# lo-synth.net
KiCad netlist of a schematic drawn in Altium Designer
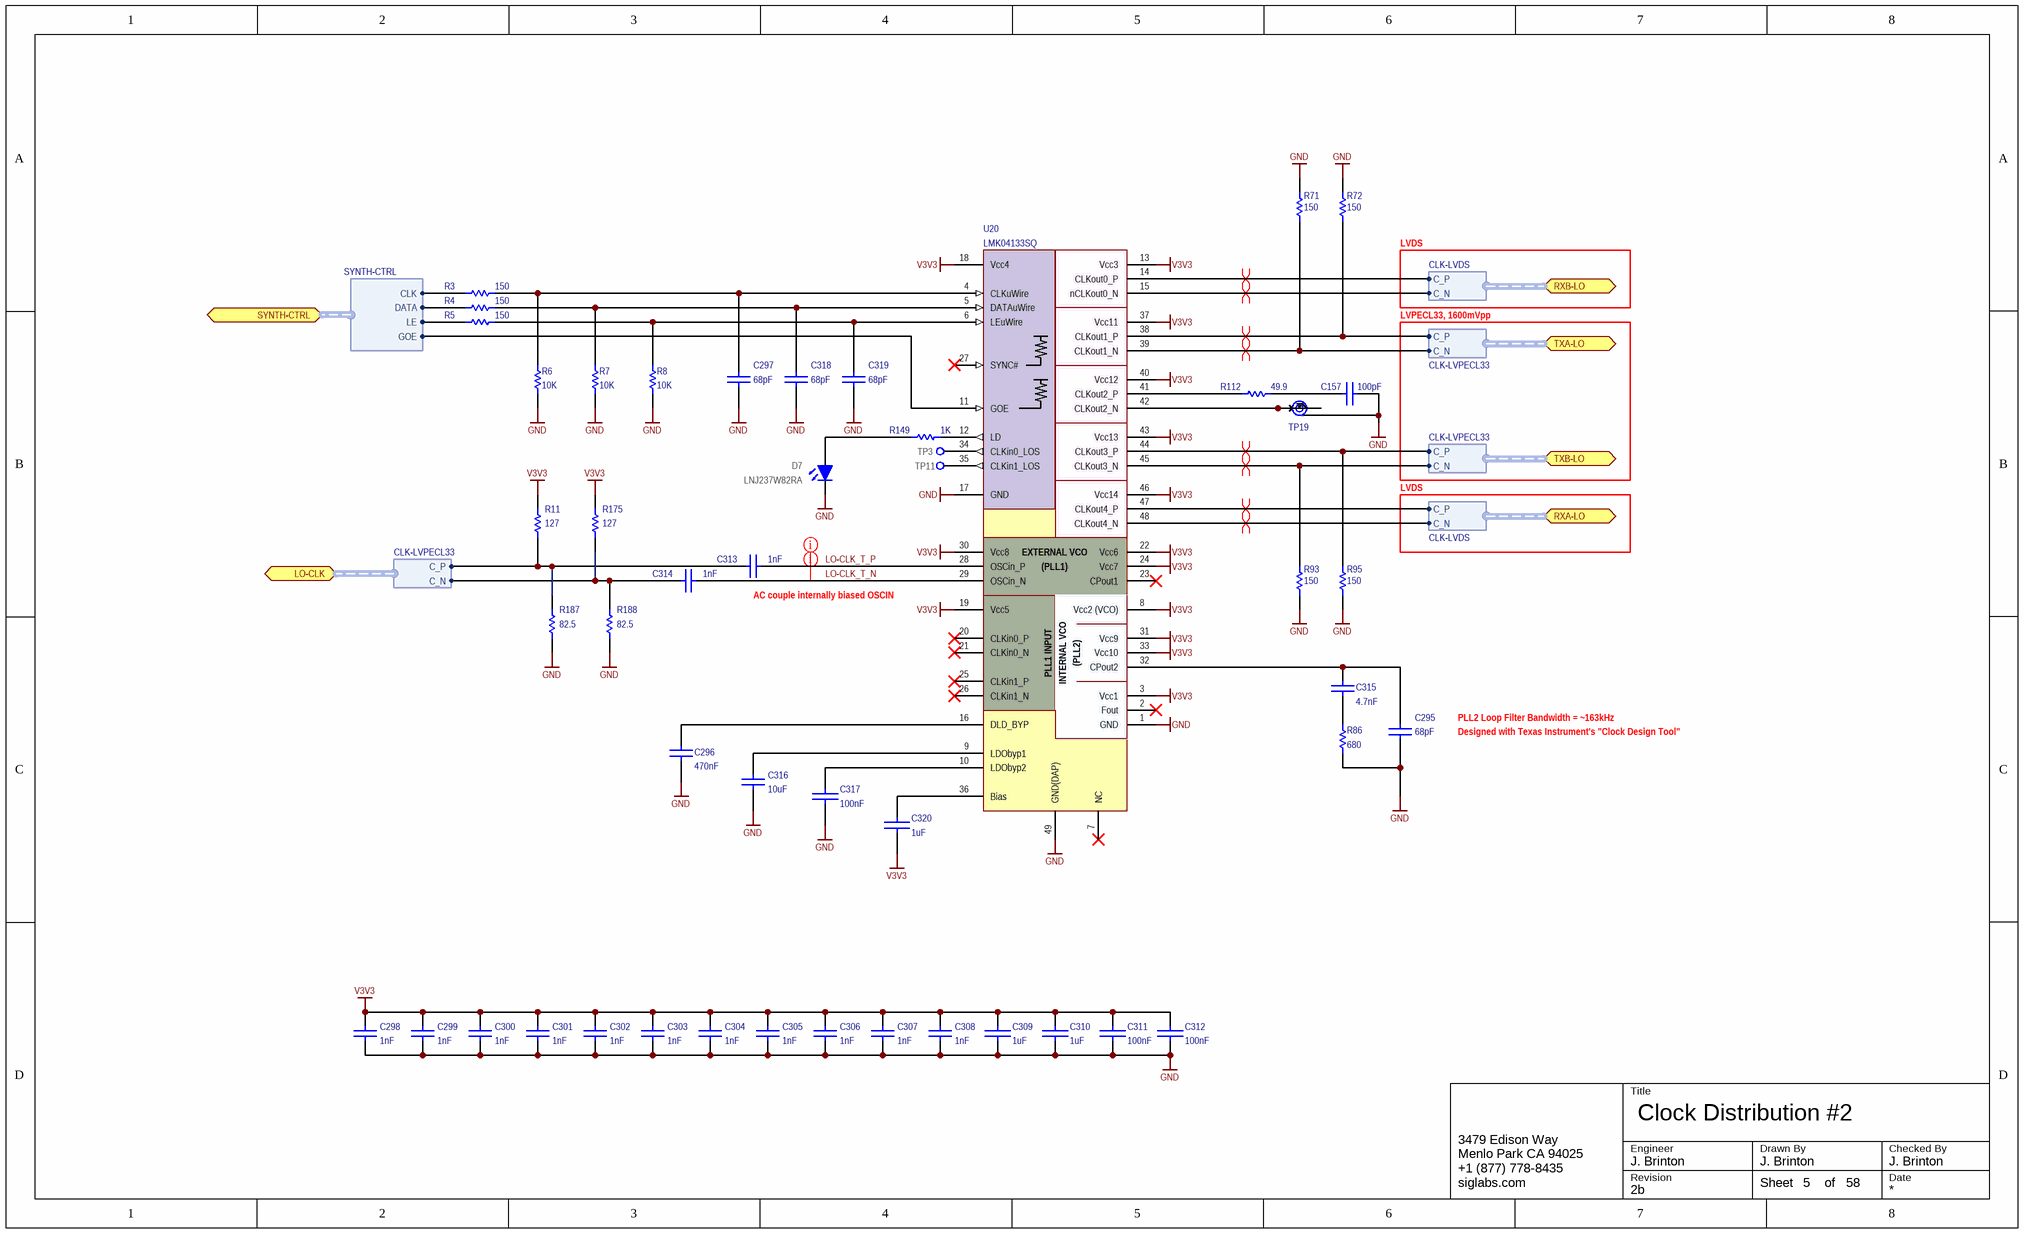
[diagram p0: lo-synth.SchDoc]

(export (version "E")
  (design (tool "Eeschema 10.0.6"))
  (components
    (comp (ref "C157")
      (value "100pF")
      (footprint "0402")
      (description "Ceramic Capacitor 100pF ±1% 25V NP0 0402")
      (fields (field (name "VOLTAGE") "25V") (field (name "MANUFACTURER") "Kemet"))
      (libsource (lib "generic") (part "CAP 0603"))
    )
    (comp (ref "C295")
      (value "68pF")
      (footprint "generic:0402")
      (description "Ceramic Capacitor 68pF ±2% 50V NP0 0402")
      (fields (field (name "VOLTAGE") "50V") (field (name "MANUFACTURER") "Murata"))
      (libsource (lib "Graviton") (part "CAP 0402"))
    )
    (comp (ref "C296")
      (value "470nF")
      (footprint "generic:0805")
      (description "Ceramic Capacitor 470nF ±10% 50V X7R 0805")
      (fields (field (name "VOLTAGE") "50V") (field (name "MANUFACTURER") "Kemet"))
      (libsource (lib "Graviton") (part "CAP 0402"))
    )
    (comp (ref "C297")
      (value "68pF")
      (footprint "generic:0402")
      (description "Ceramic Capacitor 68pF ±2% 50V NP0 0402")
      (fields (field (name "VOLTAGE") "50V") (field (name "MANUFACTURER") "Murata"))
      (libsource (lib "Graviton") (part "CAP 0402"))
    )
    (comp (ref "C298")
      (value "1nF")
      (footprint "generic:0402")
      (description "Ceramic Capacitor 1nF ±5% 50V NP0 0402")
      (fields (field (name "VOLTAGE") "50V") (field (name "MANUFACTURER") "Murata"))
      (libsource (lib "Graviton") (part "CAP 0402"))
    )
    (comp (ref "C299")
      (value "1nF")
      (footprint "generic:0402")
      (description "Ceramic Capacitor 1nF ±5% 50V NP0 0402")
      (fields (field (name "VOLTAGE") "50V") (field (name "MANUFACTURER") "Murata"))
      (libsource (lib "Graviton") (part "CAP 0402"))
    )
    (comp (ref "C300")
      (value "1nF")
      (footprint "generic:0402")
      (description "Ceramic Capacitor 1nF ±5% 50V NP0 0402")
      (fields (field (name "VOLTAGE") "50V") (field (name "MANUFACTURER") "Murata"))
      (libsource (lib "Graviton") (part "CAP 0402"))
    )
    (comp (ref "C301")
      (value "1nF")
      (footprint "generic:0402")
      (description "Ceramic Capacitor 1nF ±5% 50V NP0 0402")
      (fields (field (name "VOLTAGE") "50V") (field (name "MANUFACTURER") "Murata"))
      (libsource (lib "Graviton") (part "CAP 0402"))
    )
    (comp (ref "C302")
      (value "1nF")
      (footprint "generic:0402")
      (description "Ceramic Capacitor 1nF ±5% 50V NP0 0402")
      (fields (field (name "VOLTAGE") "50V") (field (name "MANUFACTURER") "Murata"))
      (libsource (lib "Graviton") (part "CAP 0402"))
    )
    (comp (ref "C303")
      (value "1nF")
      (footprint "generic:0402")
      (description "Ceramic Capacitor 1nF ±5% 50V NP0 0402")
      (fields (field (name "VOLTAGE") "50V") (field (name "MANUFACTURER") "Murata"))
      (libsource (lib "Graviton") (part "CAP 0402"))
    )
    (comp (ref "C304")
      (value "1nF")
      (footprint "generic:0402")
      (description "Ceramic Capacitor 1nF ±5% 50V NP0 0402")
      (fields (field (name "VOLTAGE") "50V") (field (name "MANUFACTURER") "Murata"))
      (libsource (lib "Graviton") (part "CAP 0402"))
    )
    (comp (ref "C305")
      (value "1nF")
      (footprint "generic:0402")
      (description "Ceramic Capacitor 1nF ±5% 50V NP0 0402")
      (fields (field (name "VOLTAGE") "50V") (field (name "MANUFACTURER") "Murata"))
      (libsource (lib "Graviton") (part "CAP 0402"))
    )
    (comp (ref "C306")
      (value "1nF")
      (footprint "generic:0402")
      (description "Ceramic Capacitor 1nF ±5% 50V NP0 0402")
      (fields (field (name "VOLTAGE") "50V") (field (name "MANUFACTURER") "Murata"))
      (libsource (lib "Graviton") (part "CAP 0402"))
    )
    (comp (ref "C307")
      (value "1nF")
      (footprint "generic:0402")
      (description "Ceramic Capacitor 1nF ±5% 50V NP0 0402")
      (fields (field (name "VOLTAGE") "50V") (field (name "MANUFACTURER") "Murata"))
      (libsource (lib "Graviton") (part "CAP 0402"))
    )
    (comp (ref "C308")
      (value "1nF")
      (footprint "generic:0402")
      (description "Ceramic Capacitor 1nF ±5% 50V NP0 0402")
      (fields (field (name "VOLTAGE") "50V") (field (name "MANUFACTURER") "Murata"))
      (libsource (lib "Graviton") (part "CAP 0402"))
    )
    (comp (ref "C309")
      (value "1uF")
      (footprint "generic:0402")
      (description "Ceramic Capacitor 1uF ±10% 10V X5R 0402")
      (fields (field (name "MANUFACTURER") "Murata") (field (name "TOLERANCE") "±10%"))
      (libsource (lib "*") (part "CAP"))
    )
    (comp (ref "C310")
      (value "1uF")
      (footprint "generic:0402")
      (description "Ceramic Capacitor 1uF ±10% 10V X5R 0402")
      (fields (field (name "MANUFACTURER") "Murata") (field (name "TOLERANCE") "±10%"))
      (libsource (lib "*") (part "CAP"))
    )
    (comp (ref "C311")
      (value "100nF")
      (footprint "generic:0402")
      (description "Ceramic Capacitor 100nF ±10% 16V X7R 0402")
      (fields (field (name "MANUFACTURER") "Murata") (field (name "VOLTAGE") "16V"))
      (libsource (lib "*") (part "CAP"))
    )
    (comp (ref "C312")
      (value "100nF")
      (footprint "generic:0402")
      (description "Ceramic Capacitor 100nF ±10% 16V X7R 0402")
      (fields (field (name "MANUFACTURER") "Murata") (field (name "VOLTAGE") "16V"))
      (libsource (lib "*") (part "CAP"))
    )
    (comp (ref "C313")
      (value "1nF")
      (footprint "generic:0402")
      (description "Ceramic Capacitor 1nF ±5% 50V NP0 0402")
      (fields (field (name "VOLTAGE") "50V") (field (name "MANUFACTURER") "Murata"))
      (libsource (lib "Graviton") (part "CAP 0402"))
    )
    (comp (ref "C314")
      (value "1nF")
      (footprint "generic:0402")
      (description "Ceramic Capacitor 1nF ±5% 50V NP0 0402")
      (fields (field (name "VOLTAGE") "50V") (field (name "MANUFACTURER") "Murata"))
      (libsource (lib "Graviton") (part "CAP 0402"))
    )
    (comp (ref "C315")
      (value "4.7nF")
      (footprint "generic:0402")
      (description "Ceramic Capacitor 4.7nF ±5% 50V X7R 0402")
      (fields (field (name "VOLTAGE") "50V") (field (name "MANUFACTURER") "Murata"))
      (libsource (lib "Graviton") (part "CAP 0402"))
    )
    (comp (ref "C316")
      (value "10uF")
      (footprint "generic:0603")
      (description "Ceramic Capacitor 10uF ±20% 25V X5R 0603")
      (fields (field (name "VOLTAGE") "25V") (field (name "MANUFACTURER") "Samsung"))
      (libsource (lib "Graviton") (part "CAP 0402"))
    )
    (comp (ref "C317")
      (value "100nF")
      (footprint "generic:0402")
      (description "Ceramic Capacitor 100nF ±10% 16V X7R 0402")
      (fields (field (name "MANUFACTURER") "Murata") (field (name "VOLTAGE") "16V"))
      (libsource (lib "*") (part "CAP"))
    )
    (comp (ref "C318")
      (value "68pF")
      (footprint "generic:0402")
      (description "Ceramic Capacitor 68pF ±2% 50V NP0 0402")
      (fields (field (name "VOLTAGE") "50V") (field (name "MANUFACTURER") "Murata"))
      (libsource (lib "Graviton") (part "CAP 0402"))
    )
    (comp (ref "C319")
      (value "68pF")
      (footprint "generic:0402")
      (description "Ceramic Capacitor 68pF ±2% 50V NP0 0402")
      (fields (field (name "VOLTAGE") "50V") (field (name "MANUFACTURER") "Murata"))
      (libsource (lib "Graviton") (part "CAP 0402"))
    )
    (comp (ref "C320")
      (value "1uF")
      (footprint "generic:0402")
      (description "Ceramic Capacitor 1uF ±10% 10V X5R 0402")
      (fields (field (name "MANUFACTURER") "Murata") (field (name "TOLERANCE") "±10%"))
      (libsource (lib "*") (part "CAP"))
    )
    (comp (ref "D7")
      (value "LNJ237W82RA")
      (footprint "0603_LED")
      (description "LED, SMT 0603, Color Red, 5mA, 1.85V")
      (fields (field (name "MANUFACTURER") "Panasonic"))
      (libsource (lib "generic") (part "LED0603RD"))
    )
    (comp (ref "R3")
      (value "150")
      (footprint "generic:0402")
      (description "Thick Film 150 ±1% 0402")
      (fields (field (name "MANUFACTURER") "Panasonic") (field (name "TOLERANCE") "±1%"))
      (libsource (lib "Graviton") (part "RES 0402"))
    )
    (comp (ref "R4")
      (value "150")
      (footprint "generic:0402")
      (description "Thick Film 150 ±1% 0402")
      (fields (field (name "MANUFACTURER") "Panasonic") (field (name "TOLERANCE") "±1%"))
      (libsource (lib "Graviton") (part "RES 0402"))
    )
    (comp (ref "R5")
      (value "150")
      (footprint "generic:0402")
      (description "Thick Film 150 ±1% 0402")
      (fields (field (name "MANUFACTURER") "Panasonic") (field (name "TOLERANCE") "±1%"))
      (libsource (lib "Graviton") (part "RES 0402"))
    )
    (comp (ref "R6")
      (value "10K")
      (footprint "generic:0402")
      (description "Thick Film 10k ±1% 0402")
      (fields (field (name "MANUFACTURER") "Panasonic") (field (name "TOLERANCE") "±1%"))
      (libsource (lib "Graviton") (part "RES 0402"))
    )
    (comp (ref "R7")
      (value "10K")
      (footprint "generic:0402")
      (description "Thick Film 10k ±1% 0402")
      (fields (field (name "MANUFACTURER") "Panasonic") (field (name "TOLERANCE") "±1%"))
      (libsource (lib "Graviton") (part "RES 0402"))
    )
    (comp (ref "R8")
      (value "10K")
      (footprint "generic:0402")
      (description "Thick Film 10k ±1% 0402")
      (fields (field (name "MANUFACTURER") "Panasonic") (field (name "TOLERANCE") "±1%"))
      (libsource (lib "Graviton") (part "RES 0402"))
    )
    (comp (ref "R11")
      (value "127")
      (footprint "generic:0402")
      (description "Thin Film Resistor 127 ±0.1% 0402")
      (fields (field (name "MANUFACTURER") "Panasonic") (field (name "TOLERANCE") "±0.1%"))
      (libsource (lib "Graviton") (part "RES 0402"))
    )
    (comp (ref "R71")
      (value "150")
      (footprint "generic:0402")
      (description "Thick Film 150 ±1% 0402")
      (fields (field (name "MANUFACTURER") "Panasonic") (field (name "TOLERANCE") "±1%"))
      (libsource (lib "Graviton") (part "RES 0402"))
    )
    (comp (ref "R72")
      (value "150")
      (footprint "generic:0402")
      (description "Thick Film 150 ±1% 0402")
      (fields (field (name "MANUFACTURER") "Panasonic") (field (name "TOLERANCE") "±1%"))
      (libsource (lib "Graviton") (part "RES 0402"))
    )
    (comp (ref "R86")
      (value "680")
      (footprint "generic:0402")
      (description "Thick Film Resistor 680 ±1% 0402")
      (fields (field (name "MANUFACTURER") "Yageo") (field (name "TOLERANCE") "±1%"))
      (libsource (lib "Graviton") (part "RES 0402"))
    )
    (comp (ref "R93")
      (value "150")
      (footprint "generic:0402")
      (description "Thick Film 150 ±1% 0402")
      (fields (field (name "MANUFACTURER") "Panasonic") (field (name "TOLERANCE") "±1%"))
      (libsource (lib "Graviton") (part "RES 0402"))
    )
    (comp (ref "R95")
      (value "150")
      (footprint "generic:0402")
      (description "Thick Film 150 ±1% 0402")
      (fields (field (name "MANUFACTURER") "Panasonic") (field (name "TOLERANCE") "±1%"))
      (libsource (lib "Graviton") (part "RES 0402"))
    )
    (comp (ref "R112")
      (value "49.9")
      (footprint "generic:0603")
      (description "Thick Film Resistor 49.9 ±1% 0603")
      (fields (field (name "MANUFACTURER") "Panasonic") (field (name "TOLERANCE") "±1%"))
      (libsource (lib "generic") (part "RES 0603"))
    )
    (comp (ref "R149")
      (value "1K")
      (footprint "generic:0402")
      (description "Thick Film Resistor 1k ±1% 0402")
      (fields (field (name "MANUFACTURER") "Yageo") (field (name "TOLERANCE") "±1%"))
      (libsource (lib "Graviton") (part "RES 0402"))
    )
    (comp (ref "R175")
      (value "127")
      (footprint "generic:0402")
      (description "Thin Film Resistor 127 ±0.1% 0402")
      (fields (field (name "MANUFACTURER") "Panasonic") (field (name "TOLERANCE") "±0.1%"))
      (libsource (lib "Graviton") (part "RES 0402"))
    )
    (comp (ref "R187")
      (value "82.5")
      (footprint "generic:0402")
      (description "Thin Film Resistor 82.5 ±0.1% 0402")
      (fields (field (name "MANUFACTURER") "Panasonic") (field (name "TOLERANCE") "±0.1%"))
      (libsource (lib "Graviton") (part "RES 0402"))
    )
    (comp (ref "R188")
      (value "82.5")
      (footprint "generic:0402")
      (description "Thin Film Resistor 82.5 ±0.1% 0402")
      (fields (field (name "MANUFACTURER") "Panasonic") (field (name "TOLERANCE") "±0.1%"))
      (libsource (lib "Graviton") (part "RES 0402"))
    )
    (comp (ref "TP3")
      (value "TEST_POINT_SMD_10")
      (footprint "generic:TEST_POINT_SMD_10")
      (description "Test Point SMD")
      (libsource (lib "generic") (part "TEST_POINT_SMD_10"))
    )
    (comp (ref "TP11")
      (value "TEST_POINT_SMD_10")
      (footprint "generic:TEST_POINT_SMD_10")
      (description "Test Point SMD")
      (libsource (lib "generic") (part "TEST_POINT_SMD_10"))
    )
    (comp (ref "TP19")
      (value "MS-180(20)")
      (footprint "MS-180(20)")
      (description "Coaxial Connector Switch")
      (fields (field (name "MANUFACTURER") "Hirose"))
      (libsource (lib "hirose") (part "MS-180(20)"))
    )
    (comp (ref "U20")
      (value "LMK04133SQ")
      (footprint "texas_instruments:RHS")
      (description "Clock Jitter Cleaner with Cascaded PLLs")
      (fields (field (name "MANUFACTURER") "Texas Instruments"))
      (libsource (lib "ti") (part "LMK04133"))
    )
  )
  (nets
    (net (code "4") (name "/CLK") (class "Default")
      (node (ref "R3") (pin "1") (pinfunction "1_1") (pintype "passive"))
    )
    (net (code "5") (name "/DATA") (class "Default")
      (node (ref "R4") (pin "1") (pinfunction "1_1") (pintype "passive"))
    )
    (net (code "6") (name "/GOE") (class "Default")
      (node (ref "U20") (pin "11") (pinfunction "GOE_11") (pintype "input"))
    )
    (net (code "7") (name "/LE") (class "Default")
      (node (ref "R5") (pin "1") (pinfunction "1_1") (pintype "passive"))
    )
    (net (code "8") (name "/LO-CLK_T_N") (class "Default")
      (node (ref "C314") (pin "1") (pinfunction "1_1") (pintype "passive"))
      (node (ref "U20") (pin "29") (pinfunction "OSCin_N_29") (pintype "passive"))
    )
    (net (code "9") (name "/LO-CLK_T_P") (class "Default")
      (node (ref "C313") (pin "1") (pinfunction "1_1") (pintype "passive"))
      (node (ref "U20") (pin "28") (pinfunction "OSCin_P_28") (pintype "passive"))
    )
    (net (code "13") (name "GND") (class "Default")
      (node (ref "C157") (pin "2") (pinfunction "2_2") (pintype "passive"))
      (node (ref "C295") (pin "1") (pinfunction "1_1") (pintype "passive"))
      (node (ref "C296") (pin "1") (pinfunction "1_1") (pintype "passive"))
      (node (ref "C297") (pin "1") (pinfunction "1_1") (pintype "passive"))
      (node (ref "C298") (pin "1") (pinfunction "1_1") (pintype "passive"))
      (node (ref "C299") (pin "1") (pinfunction "1_1") (pintype "passive"))
      (node (ref "C300") (pin "1") (pinfunction "1_1") (pintype "passive"))
      (node (ref "C301") (pin "1") (pinfunction "1_1") (pintype "passive"))
      (node (ref "C302") (pin "1") (pinfunction "1_1") (pintype "passive"))
      (node (ref "C303") (pin "1") (pinfunction "1_1") (pintype "passive"))
      (node (ref "C304") (pin "1") (pinfunction "1_1") (pintype "passive"))
      (node (ref "C305") (pin "1") (pinfunction "1_1") (pintype "passive"))
      (node (ref "C306") (pin "1") (pinfunction "1_1") (pintype "passive"))
      (node (ref "C307") (pin "1") (pinfunction "1_1") (pintype "passive"))
      (node (ref "C308") (pin "1") (pinfunction "1_1") (pintype "passive"))
      (node (ref "C309") (pin "1") (pinfunction "1_1") (pintype "passive"))
      (node (ref "C310") (pin "1") (pinfunction "1_1") (pintype "passive"))
      (node (ref "C311") (pin "1") (pinfunction "1_1") (pintype "passive"))
      (node (ref "C312") (pin "1") (pinfunction "1_1") (pintype "passive"))
      (node (ref "C316") (pin "1") (pinfunction "1_1") (pintype "passive"))
      (node (ref "C317") (pin "1") (pinfunction "1_1") (pintype "passive"))
      (node (ref "C318") (pin "1") (pinfunction "1_1") (pintype "passive"))
      (node (ref "C319") (pin "1") (pinfunction "1_1") (pintype "passive"))
      (node (ref "D7") (pin "2") (pinfunction "K_2") (pintype "passive"))
      (node (ref "R187") (pin "1") (pinfunction "1_1") (pintype "passive"))
      (node (ref "R188") (pin "1") (pinfunction "1_1") (pintype "passive"))
      (node (ref "R6") (pin "1") (pinfunction "1_1") (pintype "passive"))
      (node (ref "R7") (pin "1") (pinfunction "1_1") (pintype "passive"))
      (node (ref "R71") (pin "2") (pinfunction "2_2") (pintype "passive"))
      (node (ref "R72") (pin "2") (pinfunction "2_2") (pintype "passive"))
      (node (ref "R8") (pin "1") (pinfunction "1_1") (pintype "passive"))
      (node (ref "R86") (pin "2") (pinfunction "2_2") (pintype "passive"))
      (node (ref "R93") (pin "1") (pinfunction "1_1") (pintype "passive"))
      (node (ref "R95") (pin "1") (pinfunction "1_1") (pintype "passive"))
      (node (ref "TP19") (pin "G") (pinfunction "GND_G") (pintype "passive"))
      (node (ref "U20") (pin "1") (pinfunction "GND_1") (pintype "power_in"))
      (node (ref "U20") (pin "17") (pinfunction "GND_17") (pintype "power_in"))
      (node (ref "U20") (pin "49") (pinfunction "GND(DAP)_49") (pintype "power_in"))
    )
    (net (code "14") (name "Net-(C157-Pad1)") (class "Default")
      (node (ref "C157") (pin "1") (pinfunction "1_1") (pintype "passive"))
      (node (ref "R112") (pin "2") (pinfunction "2_2") (pintype "passive"))
    )
    (net (code "15") (name "Net-(C313-Pad2)") (class "Default")
      (node (ref "C313") (pin "2") (pinfunction "2_2") (pintype "passive"))
      (node (ref "R11") (pin "1") (pinfunction "1_1") (pintype "passive"))
      (node (ref "R187") (pin "2") (pinfunction "2_2") (pintype "passive"))
    )
    (net (code "16") (name "Net-(C314-Pad2)") (class "Default")
      (node (ref "C314") (pin "2") (pinfunction "2_2") (pintype "passive"))
      (node (ref "R175") (pin "1") (pinfunction "1_1") (pintype "passive"))
      (node (ref "R188") (pin "2") (pinfunction "2_2") (pintype "passive"))
    )
    (net (code "17") (name "Net-(C315-Pad1)") (class "Default")
      (node (ref "C315") (pin "1") (pinfunction "1_1") (pintype "passive"))
      (node (ref "R86") (pin "1") (pinfunction "1_1") (pintype "passive"))
    )
    (net (code "18") (name "Net-(D7-A)") (class "Default")
      (node (ref "D7") (pin "1") (pinfunction "A_1") (pintype "passive"))
      (node (ref "R149") (pin "1") (pinfunction "1_1") (pintype "passive"))
    )
    (net (code "19") (name "Net-(TP19-IN)") (class "Default")
      (node (ref "TP19") (pin "A") (pinfunction "OUT_A") (pintype "passive"))
      (node (ref "TP19") (pin "C") (pinfunction "IN_C") (pintype "passive"))
      (node (ref "U20") (pin "42") (pinfunction "CLKout2_N_42") (pintype "passive"))
    )
    (net (code "20") (name "Net-(U20-Bias)") (class "Default")
      (node (ref "C320") (pin "2") (pinfunction "2_2") (pintype "passive"))
      (node (ref "U20") (pin "36") (pinfunction "Bias_36") (pintype "passive"))
    )
    (net (code "21") (name "Net-(U20-CLKin0_LOS)") (class "Default")
      (node (ref "TP3") (pin "1") (pinfunction "1_1") (pintype "passive"))
      (node (ref "U20") (pin "34") (pinfunction "CLKin0_LOS_34") (pintype "output"))
    )
    (net (code "22") (name "Net-(U20-CLKin1_LOS)") (class "Default")
      (node (ref "TP11") (pin "1") (pinfunction "1_1") (pintype "passive"))
      (node (ref "U20") (pin "35") (pinfunction "CLKin1_LOS_35") (pintype "output"))
    )
    (net (code "23") (name "Net-(U20-CLKout1_N)") (class "Default")
      (node (ref "R71") (pin "1") (pinfunction "1_1") (pintype "passive"))
      (node (ref "U20") (pin "39") (pinfunction "CLKout1_N_39") (pintype "passive"))
    )
    (net (code "24") (name "Net-(U20-CLKout1_P)") (class "Default")
      (node (ref "R72") (pin "1") (pinfunction "1_1") (pintype "passive"))
      (node (ref "U20") (pin "38") (pinfunction "CLKout1_P_38") (pintype "passive"))
    )
    (net (code "25") (name "Net-(U20-CLKout2_P)") (class "Default")
      (node (ref "R112") (pin "1") (pinfunction "1_1") (pintype "passive"))
      (node (ref "U20") (pin "41") (pinfunction "CLKout2_P_41") (pintype "passive"))
    )
    (net (code "26") (name "Net-(U20-CLKout3_N)") (class "Default")
      (node (ref "R93") (pin "2") (pinfunction "2_2") (pintype "passive"))
      (node (ref "U20") (pin "45") (pinfunction "CLKout3_N_45") (pintype "passive"))
    )
    (net (code "27") (name "Net-(U20-CLKout3_P)") (class "Default")
      (node (ref "R95") (pin "2") (pinfunction "2_2") (pintype "passive"))
      (node (ref "U20") (pin "44") (pinfunction "CLKout3_P_44") (pintype "passive"))
    )
    (net (code "28") (name "Net-(U20-CLKuWire)") (class "Default")
      (node (ref "C297") (pin "2") (pinfunction "2_2") (pintype "passive"))
      (node (ref "R3") (pin "2") (pinfunction "2_2") (pintype "passive"))
      (node (ref "R6") (pin "2") (pinfunction "2_2") (pintype "passive"))
      (node (ref "U20") (pin "4") (pinfunction "CLKuWire_4") (pintype "input"))
    )
    (net (code "29") (name "Net-(U20-CPout2)") (class "Default")
      (node (ref "C295") (pin "2") (pinfunction "2_2") (pintype "passive"))
      (node (ref "C315") (pin "2") (pinfunction "2_2") (pintype "passive"))
      (node (ref "U20") (pin "32") (pinfunction "CPout2_32") (pintype "passive"))
    )
    (net (code "30") (name "Net-(U20-DATAuWire)") (class "Default")
      (node (ref "C318") (pin "2") (pinfunction "2_2") (pintype "passive"))
      (node (ref "R4") (pin "2") (pinfunction "2_2") (pintype "passive"))
      (node (ref "R7") (pin "2") (pinfunction "2_2") (pintype "passive"))
      (node (ref "U20") (pin "5") (pinfunction "DATAuWire_5") (pintype "input"))
    )
    (net (code "31") (name "Net-(U20-DLD_BYP)") (class "Default")
      (node (ref "C296") (pin "2") (pinfunction "2_2") (pintype "passive"))
      (node (ref "U20") (pin "16") (pinfunction "DLD_BYP_16") (pintype "passive"))
    )
    (net (code "32") (name "Net-(U20-LD)") (class "Default")
      (node (ref "R149") (pin "2") (pinfunction "2_2") (pintype "passive"))
      (node (ref "U20") (pin "12") (pinfunction "LD_12") (pintype "output"))
    )
    (net (code "33") (name "Net-(U20-LDObyp1)") (class "Default")
      (node (ref "C316") (pin "2") (pinfunction "2_2") (pintype "passive"))
      (node (ref "U20") (pin "9") (pinfunction "LDObyp1_9") (pintype "passive"))
    )
    (net (code "34") (name "Net-(U20-LDObyp2)") (class "Default")
      (node (ref "C317") (pin "2") (pinfunction "2_2") (pintype "passive"))
      (node (ref "U20") (pin "10") (pinfunction "LDObyp2_10") (pintype "passive"))
    )
    (net (code "35") (name "Net-(U20-LEuWire)") (class "Default")
      (node (ref "C319") (pin "2") (pinfunction "2_2") (pintype "passive"))
      (node (ref "R5") (pin "2") (pinfunction "2_2") (pintype "passive"))
      (node (ref "R8") (pin "2") (pinfunction "2_2") (pintype "passive"))
      (node (ref "U20") (pin "6") (pinfunction "LEuWire_6") (pintype "input"))
    )
    (net (code "36") (name "V3V3") (class "Default")
      (node (ref "C298") (pin "2") (pinfunction "2_2") (pintype "passive"))
      (node (ref "C299") (pin "2") (pinfunction "2_2") (pintype "passive"))
      (node (ref "C300") (pin "2") (pinfunction "2_2") (pintype "passive"))
      (node (ref "C301") (pin "2") (pinfunction "2_2") (pintype "passive"))
      (node (ref "C302") (pin "2") (pinfunction "2_2") (pintype "passive"))
      (node (ref "C303") (pin "2") (pinfunction "2_2") (pintype "passive"))
      (node (ref "C304") (pin "2") (pinfunction "2_2") (pintype "passive"))
      (node (ref "C305") (pin "2") (pinfunction "2_2") (pintype "passive"))
      (node (ref "C306") (pin "2") (pinfunction "2_2") (pintype "passive"))
      (node (ref "C307") (pin "2") (pinfunction "2_2") (pintype "passive"))
      (node (ref "C308") (pin "2") (pinfunction "2_2") (pintype "passive"))
      (node (ref "C309") (pin "2") (pinfunction "2_2") (pintype "passive"))
      (node (ref "C310") (pin "2") (pinfunction "2_2") (pintype "passive"))
      (node (ref "C311") (pin "2") (pinfunction "2_2") (pintype "passive"))
      (node (ref "C312") (pin "2") (pinfunction "2_2") (pintype "passive"))
      (node (ref "C320") (pin "1") (pinfunction "1_1") (pintype "passive"))
      (node (ref "R11") (pin "2") (pinfunction "2_2") (pintype "passive"))
      (node (ref "R175") (pin "2") (pinfunction "2_2") (pintype "passive"))
      (node (ref "U20") (pin "13") (pinfunction "Vcc3_13") (pintype "power_in"))
      (node (ref "U20") (pin "18") (pinfunction "Vcc4_18") (pintype "power_in"))
      (node (ref "U20") (pin "19") (pinfunction "Vcc5_19") (pintype "power_in"))
      (node (ref "U20") (pin "22") (pinfunction "Vcc6_22") (pintype "power_in"))
      (node (ref "U20") (pin "24") (pinfunction "Vcc7_24") (pintype "power_in"))
      (node (ref "U20") (pin "3") (pinfunction "Vcc1_3") (pintype "power_in"))
      (node (ref "U20") (pin "30") (pinfunction "Vcc8_30") (pintype "power_in"))
      (node (ref "U20") (pin "31") (pinfunction "Vcc9_31") (pintype "power_in"))
      (node (ref "U20") (pin "33") (pinfunction "Vcc10_33") (pintype "power_in"))
      (node (ref "U20") (pin "37") (pinfunction "Vcc11_37") (pintype "power_in"))
      (node (ref "U20") (pin "40") (pinfunction "Vcc12_40") (pintype "power_in"))
      (node (ref "U20") (pin "43") (pinfunction "Vcc13_43") (pintype "power_in"))
      (node (ref "U20") (pin "46") (pinfunction "Vcc14_46") (pintype "power_in"))
      (node (ref "U20") (pin "8") (pinfunction "Vcc2_(VCO)_8") (pintype "power_in"))
    )
    (net (code "37") (name "unconnected-(U20-CLKin0_N-Pad21)") (class "Default")
      (node (ref "U20") (pin "21") (pinfunction "CLKin0_N_21") (pintype "passive+no_connect"))
    )
    (net (code "38") (name "unconnected-(U20-CLKin0_P-Pad20)") (class "Default")
      (node (ref "U20") (pin "20") (pinfunction "CLKin0_P_20") (pintype "passive+no_connect"))
    )
    (net (code "39") (name "unconnected-(U20-CLKin1_N-Pad26)") (class "Default")
      (node (ref "U20") (pin "26") (pinfunction "CLKin1_N_26") (pintype "passive+no_connect"))
    )
    (net (code "40") (name "unconnected-(U20-CLKin1_P-Pad25)") (class "Default")
      (node (ref "U20") (pin "25") (pinfunction "CLKin1_P_25") (pintype "passive+no_connect"))
    )
    (net (code "41") (name "unconnected-(U20-CLKout0_P-Pad14)") (class "Default")
      (node (ref "U20") (pin "14") (pinfunction "CLKout0_P_14") (pintype "passive"))
    )
    (net (code "42") (name "unconnected-(U20-CLKout4_N-Pad48)") (class "Default")
      (node (ref "U20") (pin "48") (pinfunction "CLKout4_N_48") (pintype "passive"))
    )
    (net (code "43") (name "unconnected-(U20-CLKout4_P-Pad47)") (class "Default")
      (node (ref "U20") (pin "47") (pinfunction "CLKout4_P_47") (pintype "passive"))
    )
    (net (code "44") (name "unconnected-(U20-CPout1-Pad23)") (class "Default")
      (node (ref "U20") (pin "23") (pinfunction "CPout1_23") (pintype "passive+no_connect"))
    )
    (net (code "45") (name "unconnected-(U20-Fout-Pad2)") (class "Default")
      (node (ref "U20") (pin "2") (pinfunction "Fout_2") (pintype "passive+no_connect"))
    )
    (net (code "46") (name "unconnected-(U20-NC-Pad7)") (class "Default")
      (node (ref "U20") (pin "7") (pinfunction "NC_7") (pintype "passive+no_connect"))
    )
    (net (code "47") (name "unconnected-(U20-SYNC#-Pad27)") (class "Default")
      (node (ref "U20") (pin "27") (pinfunction "SYNC#_27") (pintype "input+no_connect"))
    )
    (net (code "48") (name "unconnected-(U20-nCLKout0_N-Pad15)") (class "Default")
      (node (ref "U20") (pin "15") (pinfunction "nCLKout0_N_15") (pintype "passive"))
    )
  )
)
